# POWER.net
KiCad netlist of a schematic drawn in Altium Designer
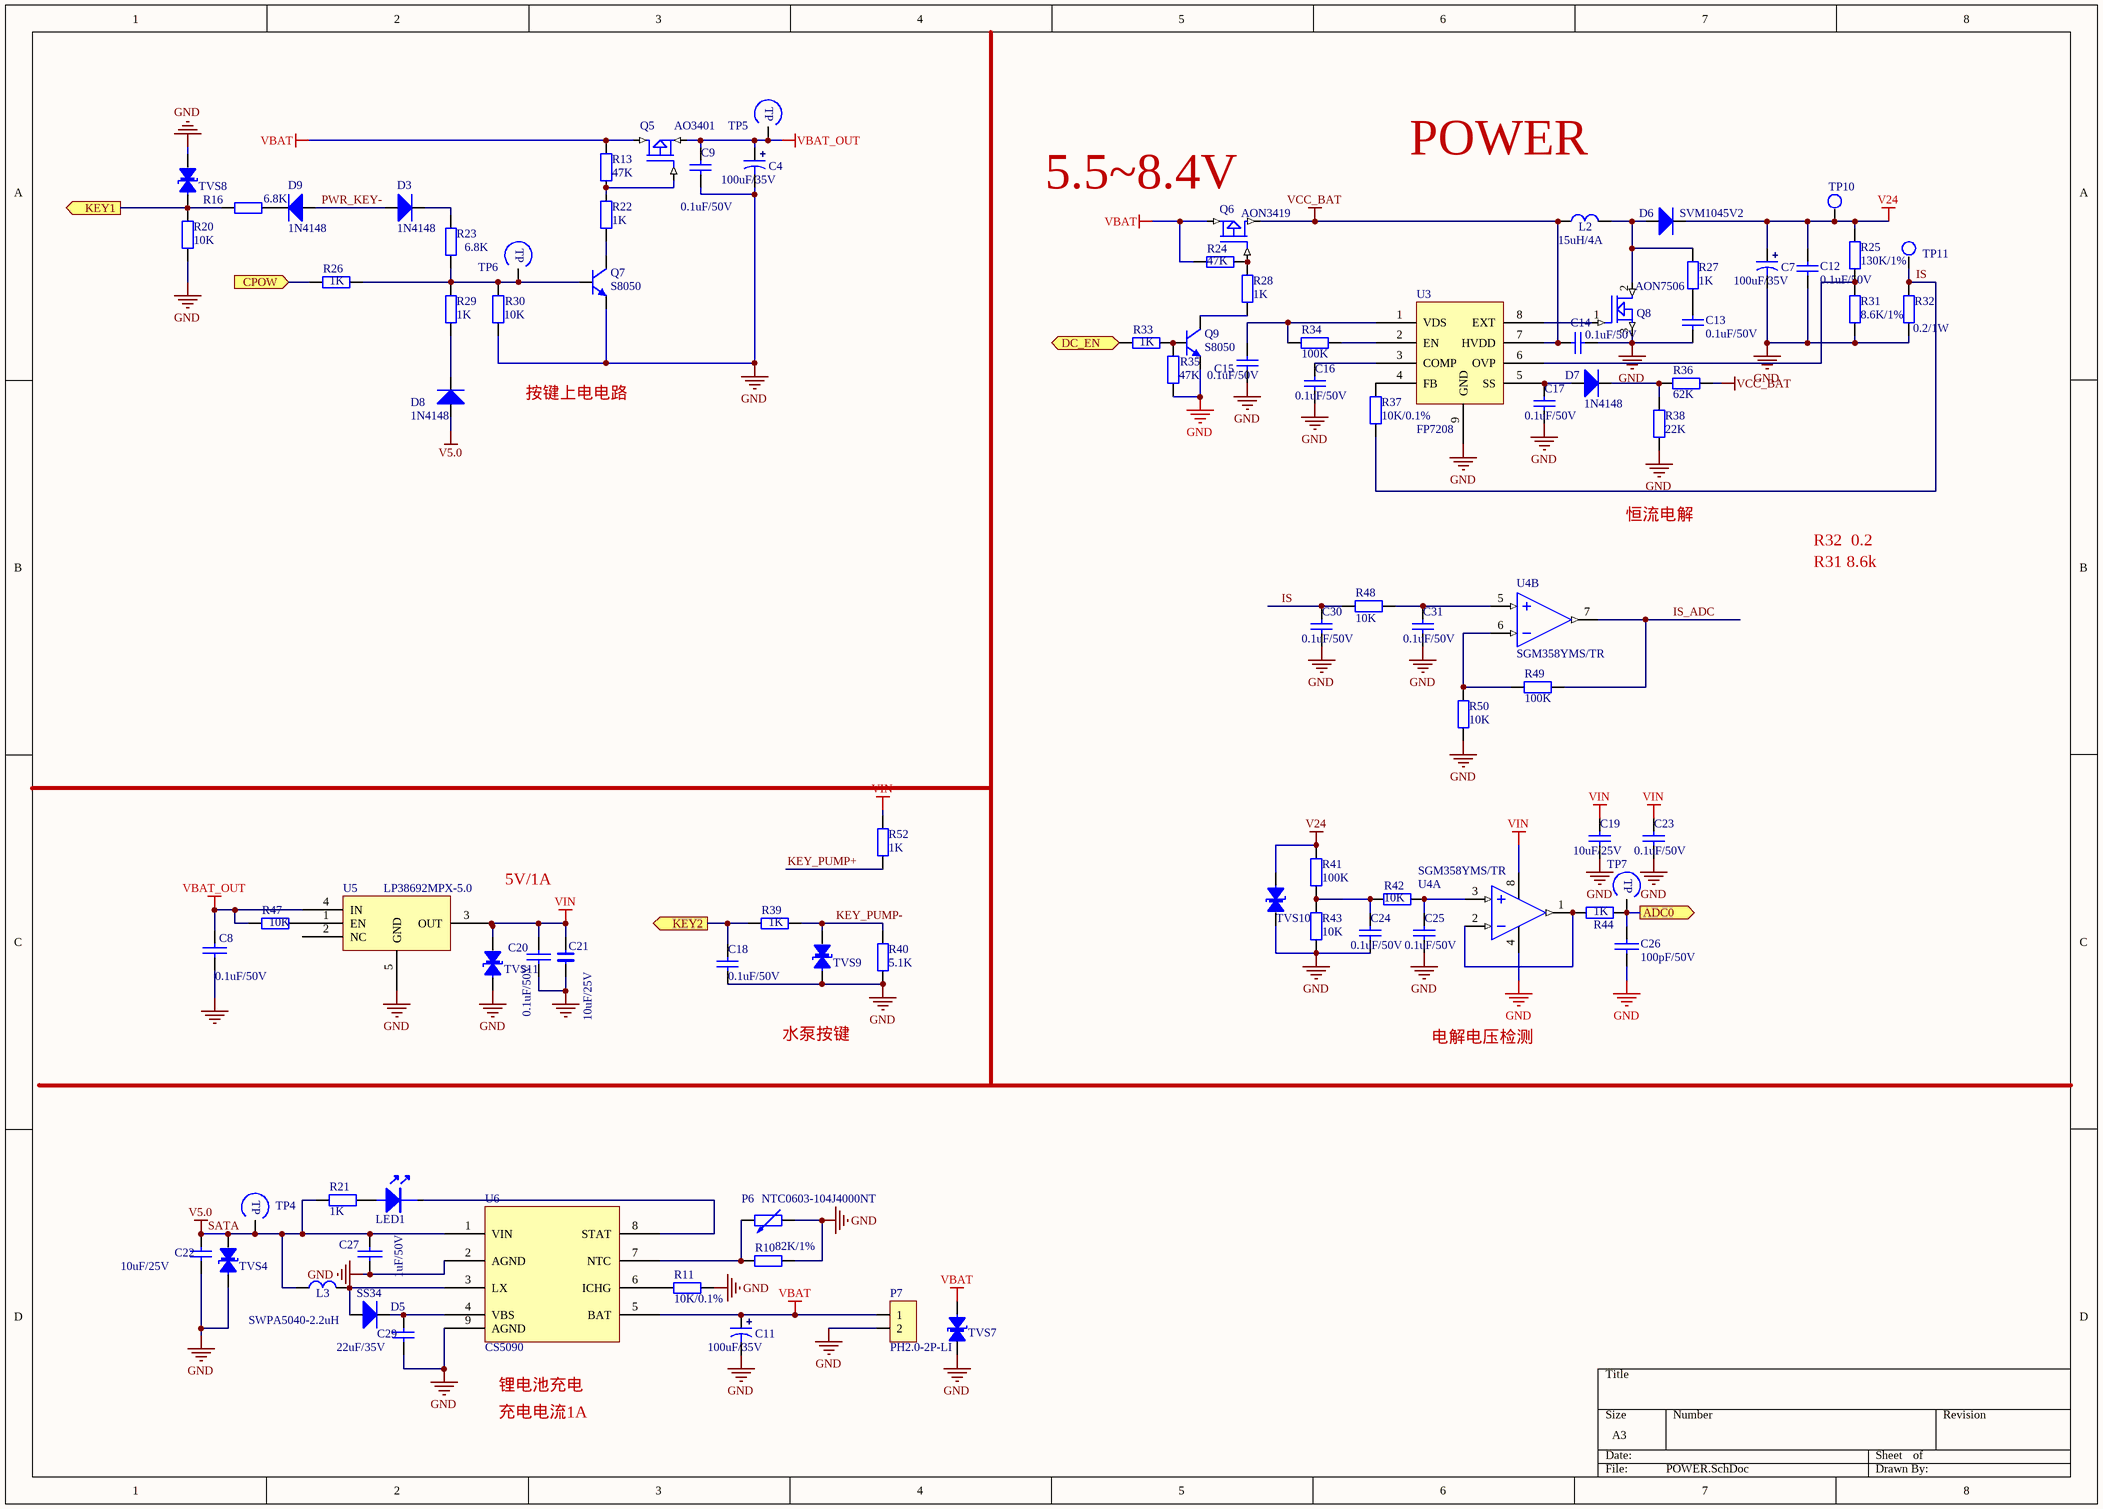
[diagram p0: POWER.SchDoc]

(export (version "E")
  (design (tool "Eeschema 10.0.6"))
  (components
    (comp (ref "C4")
      (value "100uF/35V")
      (footprint "6*8")
      (description "电解电容")
      (libsource (lib "XiaoyI") (part "CAP2"))
    )
    (comp (ref "C7")
      (value "100uF/35V")
      (footprint "6*8")
      (description "电解电容")
      (libsource (lib "XiaoyI") (part "CAP2"))
    )
    (comp (ref "C8")
      (value "0.1uF/50V")
      (footprint "SMD-0603C")
      (description "Capacitor")
      (libsource (lib "*") (part "CAP"))
    )
    (comp (ref "C9")
      (value "0.1uF/50V")
      (footprint "SMD-0603C")
      (description "贴片电容 10%")
      (libsource (lib "XiaoyI") (part "CAP4"))
    )
    (comp (ref "C11")
      (value "100uF/35V")
      (footprint "6*8")
      (description "电解电容")
      (libsource (lib "XiaoyI") (part "CAP2"))
    )
    (comp (ref "C12")
      (value "0.1uF/50V")
      (footprint "SMD-0603C")
      (description "贴片电容 10%")
      (libsource (lib "XiaoyI") (part "CAP4"))
    )
    (comp (ref "C13")
      (value "0.1uF/50V")
      (footprint "SMD-0603C")
      (description "贴片电容 10%")
      (libsource (lib "XiaoyI") (part "CAP4"))
    )
    (comp (ref "C14")
      (value "0.1uF/50V")
      (footprint "SMD-0603C")
      (description "贴片电容 10%")
      (libsource (lib "XiaoyI") (part "CAP4"))
    )
    (comp (ref "C15")
      (value "0.1uF/50V")
      (footprint "SMD-0603C")
      (description "贴片电容 10%")
      (libsource (lib "XiaoyI") (part "CAP4"))
    )
    (comp (ref "C16")
      (value "0.1uF/50V")
      (footprint "SMD-0603C")
      (description "贴片电容 10%")
      (libsource (lib "XiaoyI") (part "CAP4"))
    )
    (comp (ref "C17")
      (value "0.1uF/50V")
      (footprint "SMD-0603C")
      (description "贴片电容 10%")
      (libsource (lib "XiaoyI") (part "CAP4"))
    )
    (comp (ref "C18")
      (value "0.1uF/50V")
      (footprint "SMD-0603C")
      (description "贴片电容 10%")
      (libsource (lib "XiaoyI") (part "CAP4"))
    )
    (comp (ref "C19")
      (value "10uF/25V")
      (footprint "SMD-0603C")
      (description "贴片电容 10%")
      (libsource (lib "XiaoyI") (part "CAP4"))
    )
    (comp (ref "C20")
      (value "0.1uF/50V")
      (footprint "SMD-0603C")
      (description "Capacitor")
      (libsource (lib "*") (part "CAP"))
    )
    (comp (ref "C21")
      (value "10uF/25V")
      (footprint "SMD-0603C")
      (description "C")
      (libsource (lib "Top") (part "C"))
    )
    (comp (ref "C22")
      (value "10uF/25V")
      (footprint "SMD-0603C")
      (description "贴片电容 20%")
      (libsource (lib "XiaoyI") (part "CAP4"))
    )
    (comp (ref "C23")
      (value "0.1uF/50V")
      (footprint "SMD-0603C")
      (description "贴片电容 10%")
      (libsource (lib "XiaoyI") (part "CAP4"))
    )
    (comp (ref "C24")
      (value "0.1uF/50V")
      (footprint "SMD-0603C")
      (description "贴片电容 10%")
      (libsource (lib "XiaoyI") (part "CAP4"))
    )
    (comp (ref "C25")
      (value "0.1uF/50V")
      (footprint "SMD-0603C")
      (description "贴片电容 10%")
      (libsource (lib "XiaoyI") (part "CAP4"))
    )
    (comp (ref "C26")
      (value "100pF/50V")
      (footprint "SMD-0603C")
      (description "贴片电容 10%")
      (libsource (lib "*") (part "CAP"))
    )
    (comp (ref "C27")
      (value "1uF/50V")
      (footprint "SMD-0603C")
      (description "Capacitor")
      (libsource (lib "*") (part "CAP"))
    )
    (comp (ref "C29")
      (value "22uF/35V")
      (footprint "SMD-0603C")
      (description "贴片电容 10%")
      (libsource (lib "XiaoyI") (part "CAP4"))
    )
    (comp (ref "C30")
      (value "0.1uF/50V")
      (footprint "SMD-0603C")
      (description "贴片电容 10%")
      (libsource (lib "XiaoyI") (part "CAP4"))
    )
    (comp (ref "C31")
      (value "0.1uF/50V")
      (footprint "SMD-0603C")
      (description "贴片电容 10%")
      (libsource (lib "XiaoyI") (part "CAP4"))
    )
    (comp (ref "D3")
      (value "1N4148")
      (footprint "SOD-523")
      (description "小封装二极管")
      (libsource (lib "XiaoyI") (part "DIODE2"))
    )
    (comp (ref "D5")
      (value "SS34")
      (footprint "DO-214-AC")
      (description "肖特基二极管")
      (libsource (lib "XiaoyI") (part "DIODE2"))
    )
    (comp (ref "D6")
      (value "SVM1045V2")
      (footprint "TO227")
      (description "肖特基二极管")
      (libsource (lib "XiaoyI") (part "DIODE2"))
    )
    (comp (ref "D7")
      (value "1N4148")
      (footprint "SOD-523")
      (description "小封装二极管")
      (libsource (lib "XiaoyI") (part "DIODE2"))
    )
    (comp (ref "D8")
      (value "1N4148")
      (footprint "SOD-523")
      (description "小封装二极管")
      (libsource (lib "XiaoyI") (part "DIODE2"))
    )
    (comp (ref "D9")
      (value "1N4148")
      (footprint "SOD-523")
      (description "小封装二极管")
      (libsource (lib "XiaoyI") (part "DIODE2"))
    )
    (comp (ref "L2")
      (value "15uH/4A")
      (footprint "INDUCTOR7*7")
      (description "10uH 1A")
      (libsource (lib "XiaoyI") (part "Inductor1"))
    )
    (comp (ref "L3")
      (value "SWPA5040-2.2uH")
      (footprint "INDUCTOR_5*5")
      (description "10uH 1A")
      (libsource (lib "XiaoyI") (part "Inductor1"))
    )
    (comp (ref "LED1")
      (value "蓝光 3528")
      (footprint "SMD-0603D")
      (description "LED 3528 蓝")
      (libsource (lib "XiaoyI") (part "LED0"))
    )
    (comp (ref "P6")
      (value "NTC0603-104J4000NT")
      (footprint "SMD-0603")
      (description "卧贴")
      (libsource (lib "ABB") (part "RES3"))
    )
    (comp (ref "P7")
      (value "PH2.0-2P-LI")
      (footprint "2*2.54mmSMT")
      (description "间距2.0mm 立贴 2Pin")
      (libsource (lib "XiaoyI") (part "SIP-2"))
    )
    (comp (ref "Q5")
      (value "AO3401")
      (footprint "SOT-23")
      (description "MOSFET P")
      (libsource (lib "ABB") (part "MOSFET P"))
    )
    (comp (ref "Q6")
      (value "AON3419")
      (footprint "DFN3*3-8")
      (description "MOSFET-P")
      (libsource (lib "XiaoyI") (part "MOSFET-P-B"))
    )
    (comp (ref "Q7")
      (value "S8050")
      (footprint "SOT-23")
      (description "NPN")
      (libsource (lib "XiaoyI") (part "NPN-1"))
    )
    (comp (ref "Q8")
      (value "AON7506")
      (footprint "DFN3*3-8")
      (description "MOSFET N")
      (libsource (lib "XiaoyI") (part "MOSFET N"))
    )
    (comp (ref "Q9")
      (value "S8050")
      (footprint "SOT-23")
      (description "NPN")
      (libsource (lib "XiaoyI") (part "NPN-1"))
    )
    (comp (ref "R10")
      (value "82K/1%")
      (footprint "SMD-0603")
      (description "贴片电阻 1%")
      (libsource (lib "") (part "RES2_3"))
    )
    (comp (ref "R11")
      (value "10K/0.1%")
      (footprint "SMD-0603")
      (description "贴片电阻 1%")
      (libsource (lib "") (part "RES2_3"))
    )
    (comp (ref "R13")
      (value "47K")
      (footprint "SMD-0603")
      (description "贴片电阻 5%")
      (libsource (lib "") (part "RES2_1"))
    )
    (comp (ref "R16")
      (value "6.8K")
      (footprint "SMD-0603")
      (description "贴片电阻 5%")
      (libsource (lib "XiaoyI") (part "RES2"))
    )
    (comp (ref "R20")
      (value "10K")
      (footprint "SMD-0603")
      (description "贴片电阻 5%")
      (libsource (lib "") (part "RES2_2"))
    )
    (comp (ref "R21")
      (value "1K")
      (footprint "SMD-0603")
      (description "贴片电阻 5%")
      (libsource (lib "XiaoyI") (part "RES2"))
    )
    (comp (ref "R22")
      (value "1K")
      (footprint "SMD-0603")
      (description "贴片电阻 5%")
      (libsource (lib "") (part "RES2_2"))
    )
    (comp (ref "R23")
      (value "6.8K")
      (footprint "SMD-0603")
      (description "贴片电阻 5%")
      (libsource (lib "") (part "RES2_2"))
    )
    (comp (ref "R24")
      (value "47K")
      (footprint "SMD-0603")
      (description "贴片电阻 5%")
      (libsource (lib "XiaoyI") (part "RES2"))
    )
    (comp (ref "R25")
      (value "130K/1%")
      (footprint "SMD-0603")
      (description "贴片电阻 5%")
      (libsource (lib "") (part "RES2_1"))
    )
    (comp (ref "R26")
      (value "1K")
      (footprint "SMD-0603")
      (description "贴片电阻 5%")
      (libsource (lib "XiaoyI") (part "RES2"))
    )
    (comp (ref "R27")
      (value "1K")
      (footprint "SMD-0603")
      (description "贴片电阻 5%")
      (libsource (lib "") (part "RES2_1"))
    )
    (comp (ref "R28")
      (value "1K")
      (footprint "SMD-0603")
      (description "贴片电阻 5%")
      (libsource (lib "") (part "RES2_1"))
    )
    (comp (ref "R29")
      (value "1K")
      (footprint "SMD-0603")
      (description "贴片电阻 5%")
      (libsource (lib "") (part "RES2_2"))
    )
    (comp (ref "R30")
      (value "10K")
      (footprint "SMD-0603")
      (description "贴片电阻 5%")
      (libsource (lib "") (part "RES2_2"))
    )
    (comp (ref "R31")
      (value "8.6K/1%")
      (footprint "SMD-0603")
      (description "贴片电阻 5%")
      (libsource (lib "") (part "RES2_1"))
    )
    (comp (ref "R32")
      (value "0.2/1W")
      (footprint "2512R")
      (description "贴片电阻 5%")
      (libsource (lib "") (part "RES2_2"))
    )
    (comp (ref "R33")
      (value "1K")
      (footprint "SMD-0603")
      (description "贴片电阻 5%")
      (libsource (lib "XiaoyI") (part "RES2"))
    )
    (comp (ref "R34")
      (value "100K")
      (footprint "SMD-0603")
      (description "贴片电阻 5%")
      (libsource (lib "XiaoyI") (part "RES2"))
    )
    (comp (ref "R35")
      (value "47K")
      (footprint "SMD-0603")
      (description "贴片电阻 5%")
      (libsource (lib "") (part "RES2_2"))
    )
    (comp (ref "R36")
      (value "62K")
      (footprint "SMD-0603")
      (description "贴片电阻 5%")
      (libsource (lib "XiaoyI") (part "RES2"))
    )
    (comp (ref "R37")
      (value "10K/0.1%")
      (footprint "SMD-0603")
      (description "贴片电阻 5%")
      (libsource (lib "") (part "RES2_2"))
    )
    (comp (ref "R38")
      (value "22K")
      (footprint "SMD-0603")
      (description "贴片电阻 5%")
      (libsource (lib "") (part "RES2_1"))
    )
    (comp (ref "R39")
      (value "1K")
      (footprint "SMD-0603")
      (description "贴片电阻 5%")
      (libsource (lib "XiaoyI") (part "RES2"))
    )
    (comp (ref "R40")
      (value "5.1K")
      (footprint "SMD-0603")
      (description "贴片电阻 5%")
      (libsource (lib "") (part "RES2_2"))
    )
    (comp (ref "R41")
      (value "100K")
      (footprint "SMD-0603")
      (description "贴片电阻 1%")
      (libsource (lib "") (part "RES0_2"))
    )
    (comp (ref "R42")
      (value "10K")
      (footprint "SMD-0603")
      (description "贴片电阻 5%")
      (libsource (lib "") (part "RES0_1"))
    )
    (comp (ref "R43")
      (value "10K")
      (footprint "SMD-0603")
      (description "贴片电阻 1%")
      (libsource (lib "") (part "RES0_2"))
    )
    (comp (ref "R44")
      (value "1K")
      (footprint "SMD-0603")
      (description "贴片电阻 1%")
      (libsource (lib "") (part "RES2_3"))
    )
    (comp (ref "R47")
      (value "10K")
      (footprint "SMD-0603")
      (description "贴片电阻 5%")
      (libsource (lib "XiaoyI") (part "RES2"))
    )
    (comp (ref "R48")
      (value "10K")
      (footprint "SMD-0603")
      (description "贴片电阻 5%")
      (libsource (lib "") (part "RES0_1"))
    )
    (comp (ref "R49")
      (value "100K")
      (footprint "SMD-0603")
      (description "贴片电阻 5%")
      (libsource (lib "") (part "RES0_3"))
    )
    (comp (ref "R50")
      (value "10K")
      (footprint "SMD-0603")
      (description "贴片电阻 5%")
      (libsource (lib "ABB") (part "RES0"))
    )
    (comp (ref "R52")
      (value "1K")
      (footprint "SMD-0603")
      (description "贴片电阻 5%")
      (libsource (lib "") (part "RES2_2"))
    )
    (comp (ref "TP4")
      (value "testpoint")
      (footprint "TP")
      (description "测试点")
      (libsource (lib "XiaoyI") (part "TP-1"))
    )
    (comp (ref "TP5")
      (value "testpoint")
      (footprint "TP")
      (description "测试点")
      (libsource (lib "XiaoyI") (part "TP-1"))
    )
    (comp (ref "TP6")
      (value "testpoint")
      (footprint "TP")
      (description "测试点")
      (libsource (lib "XiaoyI") (part "TP-1"))
    )
    (comp (ref "TP7")
      (value "testpoint")
      (footprint "TP")
      (description "测试点")
      (libsource (lib "XiaoyI") (part "TP-1"))
    )
    (comp (ref "TP10") (value "TPS") (footprint "HOLE") (libsource (lib "stm32") (part "TPS")))
    (comp (ref "TP11") (value "TPS") (footprint "HOLE") (libsource (lib "stm32") (part "TPS")))
    (comp (ref "TVS4")
      (value "ESD5Z5.0CT1G")
      (footprint "SOD-523")
      (description "ESD二极管")
      (libsource (lib "XiaoyI") (part "TVS-1"))
    )
    (comp (ref "TVS7")
      (value "SMF9.0CA")
      (footprint "SOD-123")
      (description "ESD二极管")
      (libsource (lib "") (part "TVS-1_1"))
    )
    (comp (ref "TVS8")
      (value "ESD5Z5.0CT1G")
      (footprint "SOD-523")
      (description "ESD二极管")
      (libsource (lib "XiaoyI") (part "TVS-1"))
    )
    (comp (ref "TVS9")
      (value "ESD5Z5.0CT1G")
      (footprint "SOD-523")
      (description "ESD二极管")
      (libsource (lib "XiaoyI") (part "TVS-1"))
    )
    (comp (ref "TVS10")
      (value "SMF24CA")
      (footprint "SOD-123")
      (description "ESD二极管")
      (libsource (lib "") (part "TVS-1_1"))
    )
    (comp (ref "TVS11")
      (value "ESD5Z5.0CT1G")
      (footprint "SOD-523")
      (description "ESD二极管")
      (libsource (lib "XiaoyI") (part "TVS-1"))
    )
    (comp (ref "U3")
      (value "FP7208")
      (footprint "SOP127P600X265_HS-9N")
      (libsource (lib "电解水杯V1.1_ZM_20210702") (part "FP7208"))
    )
    (comp (ref "U4")
      (value "SGM358YMS/TR")
      (footprint "MSOP-8")
      (description "运放")
      (libsource (lib "电解水杯V1.1_ZM_20210702") (part "LM358"))
    )
    (comp (ref "U5")
      (value "LP38692MPX-5.0")
      (footprint "SOT223-5")
      (libsource (lib "stm32") (part "LP38692MPX-5.0"))
    )
    (comp (ref "U6")
      (value "CS5090")
      (footprint "SOP127P600X265_HS-9N")
      (libsource (lib "电解水杯V1.1_ZM_20210702") (part "CS5095E"))
    )
  )
  (nets
    (net (code "1") (name "/ADC0") (class "Default")
      (node (ref "C26") (pin "1") (pinfunction "1_1") (pintype "passive"))
      (node (ref "R44") (pin "1") (pinfunction "1_1") (pintype "passive"))
      (node (ref "TP7") (pin "1") (pinfunction "1_1") (pintype "passive"))
    )
    (net (code "2") (name "/CPOW") (class "Default")
      (node (ref "R26") (pin "1") (pinfunction "1_1") (pintype "passive"))
    )
    (net (code "3") (name "/DC_EN") (class "Default")
      (node (ref "R33") (pin "1") (pinfunction "1_1") (pintype "passive"))
    )
    (net (code "4") (name "/IS") (class "Default")
      (node (ref "C30") (pin "2") (pinfunction "2_2") (pintype "passive"))
      (node (ref "R32") (pin "2") (pinfunction "2_2") (pintype "passive"))
      (node (ref "R37") (pin "1") (pinfunction "1_1") (pintype "passive"))
      (node (ref "R48") (pin "2") (pinfunction "2_2") (pintype "passive"))
      (node (ref "TP11") (pin "1") (pinfunction "1_1") (pintype "passive"))
    )
    (net (code "5") (name "/IS_ADC") (class "Default")
      (node (ref "R49") (pin "2") (pinfunction "2_2") (pintype "passive"))
      (node (ref "U4") (pin "7") (pinfunction "OUT2_7") (pintype "output"))
    )
    (net (code "6") (name "/KEY1") (class "Default")
      (node (ref "R16") (pin "1") (pinfunction "1_1") (pintype "passive"))
      (node (ref "R20") (pin "2") (pinfunction "2_2") (pintype "passive"))
      (node (ref "TVS8") (pin "2") (pinfunction "B_2") (pintype "passive"))
    )
    (net (code "7") (name "/KEY2") (class "Default")
      (node (ref "C18") (pin "2") (pinfunction "2_2") (pintype "passive"))
      (node (ref "R39") (pin "1") (pinfunction "1_1") (pintype "passive"))
    )
    (net (code "8") (name "/KEY_PUMP+") (class "Default")
      (node (ref "R52") (pin "1") (pinfunction "1_1") (pintype "passive"))
    )
    (net (code "9") (name "/KEY_PUMP-") (class "Default")
      (node (ref "R39") (pin "2") (pinfunction "2_2") (pintype "passive"))
      (node (ref "R40") (pin "2") (pinfunction "2_2") (pintype "passive"))
      (node (ref "TVS9") (pin "1") (pinfunction "A_1") (pintype "passive"))
    )
    (net (code "10") (name "/PWR_KEY-") (class "Default")
      (node (ref "D3") (pin "1") (pinfunction "A_1") (pintype "passive"))
      (node (ref "D9") (pin "1") (pinfunction "A_1") (pintype "passive"))
    )
    (net (code "11") (name "GND") (class "Default")
      (node (ref "C11") (pin "2") (pinfunction "2_2") (pintype "passive"))
      (node (ref "C12") (pin "2") (pinfunction "2_2") (pintype "passive"))
      (node (ref "C13") (pin "2") (pinfunction "2_2") (pintype "passive"))
      (node (ref "C14") (pin "1") (pinfunction "1_1") (pintype "passive"))
      (node (ref "C15") (pin "1") (pinfunction "1_1") (pintype "passive"))
      (node (ref "C16") (pin "1") (pinfunction "1_1") (pintype "passive"))
      (node (ref "C17") (pin "1") (pinfunction "1_1") (pintype "passive"))
      (node (ref "C18") (pin "1") (pinfunction "1_1") (pintype "passive"))
      (node (ref "C19") (pin "1") (pinfunction "1_1") (pintype "passive"))
      (node (ref "C20") (pin "2") (pinfunction "2_2") (pintype "passive"))
      (node (ref "C21") (pin "1") (pintype "passive"))
      (node (ref "C22") (pin "1") (pinfunction "1_1") (pintype "passive"))
      (node (ref "C23") (pin "1") (pinfunction "1_1") (pintype "passive"))
      (node (ref "C24") (pin "1") (pinfunction "1_1") (pintype "passive"))
      (node (ref "C25") (pin "1") (pinfunction "1_1") (pintype "passive"))
      (node (ref "C26") (pin "2") (pinfunction "2_2") (pintype "passive"))
      (node (ref "C27") (pin "2") (pinfunction "2_2") (pintype "passive"))
      (node (ref "C29") (pin "1") (pinfunction "1_1") (pintype "passive"))
      (node (ref "C30") (pin "1") (pinfunction "1_1") (pintype "passive"))
      (node (ref "C31") (pin "1") (pinfunction "1_1") (pintype "passive"))
      (node (ref "C4") (pin "2") (pinfunction "2_2") (pintype "passive"))
      (node (ref "C7") (pin "2") (pinfunction "2_2") (pintype "passive"))
      (node (ref "C8") (pin "2") (pinfunction "2_2") (pintype "passive"))
      (node (ref "C9") (pin "1") (pinfunction "1_1") (pintype "passive"))
      (node (ref "P6") (pin "1") (pinfunction "1_1") (pintype "passive"))
      (node (ref "P7") (pin "2") (pinfunction "2_2") (pintype "passive"))
      (node (ref "Q7") (pin "2") (pinfunction "E_2") (pintype "passive"))
      (node (ref "Q8") (pin "3") (pinfunction "S_3") (pintype "output"))
      (node (ref "Q9") (pin "2") (pinfunction "E_2") (pintype "passive"))
      (node (ref "R10") (pin "1") (pinfunction "1_1") (pintype "passive"))
      (node (ref "R11") (pin "1") (pinfunction "1_1") (pintype "passive"))
      (node (ref "R20") (pin "1") (pinfunction "1_1") (pintype "passive"))
      (node (ref "R30") (pin "1") (pinfunction "1_1") (pintype "passive"))
      (node (ref "R31") (pin "2") (pinfunction "2_2") (pintype "passive"))
      (node (ref "R32") (pin "1") (pinfunction "1_1") (pintype "passive"))
      (node (ref "R35") (pin "1") (pinfunction "1_1") (pintype "passive"))
      (node (ref "R38") (pin "2") (pinfunction "2_2") (pintype "passive"))
      (node (ref "R40") (pin "1") (pinfunction "1_1") (pintype "passive"))
      (node (ref "R43") (pin "1") (pinfunction "1_1") (pintype "passive"))
      (node (ref "R50") (pin "2") (pinfunction "2_2") (pintype "passive"))
      (node (ref "TVS10") (pin "1") (pinfunction "A_1") (pintype "passive"))
      (node (ref "TVS11") (pin "2") (pinfunction "B_2") (pintype "passive"))
      (node (ref "TVS4") (pin "2") (pinfunction "B_2") (pintype "passive"))
      (node (ref "TVS7") (pin "1") (pinfunction "A_1") (pintype "passive"))
      (node (ref "TVS8") (pin "1") (pinfunction "A_1") (pintype "passive"))
      (node (ref "TVS9") (pin "2") (pinfunction "B_2") (pintype "passive"))
      (node (ref "U3") (pin "9") (pinfunction "GND_9") (pintype "passive"))
      (node (ref "U4") (pin "4") (pinfunction "V-_4") (pintype "power_in"))
      (node (ref "U5") (pin "5") (pinfunction "GND_5") (pintype "passive"))
      (node (ref "U6") (pin "2") (pinfunction "AGND_2") (pintype "passive"))
      (node (ref "U6") (pin "9") (pinfunction "AGND_9") (pintype "passive"))
    )
    (net (code "12") (name "Net-(C13-Pad1)") (class "Default")
      (node (ref "C13") (pin "1") (pinfunction "1_1") (pintype "passive"))
      (node (ref "R27") (pin "2") (pinfunction "2_2") (pintype "passive"))
    )
    (net (code "13") (name "Net-(C24-Pad2)") (class "Default")
      (node (ref "C24") (pin "2") (pinfunction "2_2") (pintype "passive"))
      (node (ref "R41") (pin "1") (pinfunction "1_1") (pintype "passive"))
      (node (ref "R42") (pin "2") (pinfunction "2_2") (pintype "passive"))
      (node (ref "R43") (pin "2") (pinfunction "2_2") (pintype "passive"))
    )
    (net (code "14") (name "Net-(D3-K)") (class "Default")
      (node (ref "D3") (pin "2") (pinfunction "K_2") (pintype "passive"))
      (node (ref "R23") (pin "2") (pinfunction "2_2") (pintype "passive"))
    )
    (net (code "15") (name "Net-(D5-A)") (class "Default")
      (node (ref "D5") (pin "1") (pinfunction "A_1") (pintype "passive"))
      (node (ref "L3") (pin "2") (pinfunction "2_2") (pintype "passive"))
      (node (ref "U6") (pin "3") (pinfunction "LX_3") (pintype "passive"))
    )
    (net (code "16") (name "Net-(D5-K)") (class "Default")
      (node (ref "C29") (pin "2") (pinfunction "2_2") (pintype "passive"))
      (node (ref "D5") (pin "2") (pinfunction "K_2") (pintype "passive"))
      (node (ref "U6") (pin "4") (pinfunction "VBS_4") (pintype "passive"))
    )
    (net (code "17") (name "Net-(D6-A)") (class "Default")
      (node (ref "D6") (pin "1") (pinfunction "A_1") (pintype "passive"))
      (node (ref "L2") (pin "2") (pinfunction "2_2") (pintype "passive"))
      (node (ref "Q8") (pin "2") (pinfunction "D_2") (pintype "input"))
      (node (ref "R27") (pin "1") (pinfunction "1_1") (pintype "passive"))
    )
    (net (code "18") (name "Net-(D7-A)") (class "Default")
      (node (ref "C17") (pin "2") (pinfunction "2_2") (pintype "passive"))
      (node (ref "D7") (pin "1") (pinfunction "A_1") (pintype "passive"))
      (node (ref "U3") (pin "5") (pinfunction "SS_5") (pintype "passive"))
    )
    (net (code "19") (name "Net-(D7-K)") (class "Default")
      (node (ref "D7") (pin "2") (pinfunction "K_2") (pintype "passive"))
      (node (ref "R36") (pin "1") (pinfunction "1_1") (pintype "passive"))
      (node (ref "R38") (pin "1") (pinfunction "1_1") (pintype "passive"))
    )
    (net (code "20") (name "Net-(D8-K)") (class "Default")
      (node (ref "D8") (pin "2") (pinfunction "K_2") (pintype "passive"))
      (node (ref "R29") (pin "1") (pinfunction "1_1") (pintype "passive"))
    )
    (net (code "21") (name "Net-(D9-K)") (class "Default")
      (node (ref "D9") (pin "2") (pinfunction "K_2") (pintype "passive"))
      (node (ref "R16") (pin "2") (pinfunction "2_2") (pintype "passive"))
    )
    (net (code "22") (name "Net-(LED1-Pad1)") (class "Default")
      (node (ref "LED1") (pin "1") (pinfunction "1_1") (pintype "passive"))
      (node (ref "R21") (pin "2") (pinfunction "2_2") (pintype "passive"))
    )
    (net (code "23") (name "Net-(Q5-G)") (class "Default")
      (node (ref "Q5") (pin "1") (pinfunction "G_1") (pintype "input"))
      (node (ref "R13") (pin "2") (pinfunction "2_2") (pintype "passive"))
      (node (ref "R22") (pin "2") (pinfunction "2_2") (pintype "passive"))
    )
    (net (code "24") (name "Net-(Q6-G)") (class "Default")
      (node (ref "Q6") (pin "1") (pinfunction "G_1") (pintype "input"))
      (node (ref "R24") (pin "2") (pinfunction "2_2") (pintype "passive"))
      (node (ref "R28") (pin "1") (pinfunction "1_1") (pintype "passive"))
    )
    (net (code "25") (name "Net-(Q7-B)") (class "Default")
      (node (ref "Q7") (pin "1") (pinfunction "B_1") (pintype "passive"))
      (node (ref "R23") (pin "1") (pinfunction "1_1") (pintype "passive"))
      (node (ref "R26") (pin "2") (pinfunction "2_2") (pintype "passive"))
      (node (ref "R29") (pin "2") (pinfunction "2_2") (pintype "passive"))
      (node (ref "R30") (pin "2") (pinfunction "2_2") (pintype "passive"))
      (node (ref "TP6") (pin "1") (pinfunction "1_1") (pintype "passive"))
    )
    (net (code "26") (name "Net-(Q7-C)") (class "Default")
      (node (ref "Q7") (pin "3") (pinfunction "C_3") (pintype "passive"))
      (node (ref "R22") (pin "1") (pinfunction "1_1") (pintype "passive"))
    )
    (net (code "27") (name "Net-(Q8-G)") (class "Default")
      (node (ref "Q8") (pin "1") (pinfunction "G_1") (pintype "input"))
      (node (ref "U3") (pin "8") (pinfunction "EXT_8") (pintype "passive"))
    )
    (net (code "28") (name "Net-(Q9-B)") (class "Default")
      (node (ref "Q9") (pin "1") (pinfunction "B_1") (pintype "passive"))
      (node (ref "R33") (pin "2") (pinfunction "2_2") (pintype "passive"))
      (node (ref "R35") (pin "2") (pinfunction "2_2") (pintype "passive"))
    )
    (net (code "29") (name "Net-(Q9-C)") (class "Default")
      (node (ref "Q9") (pin "3") (pinfunction "C_3") (pintype "passive"))
      (node (ref "R28") (pin "2") (pinfunction "2_2") (pintype "passive"))
    )
    (net (code "30") (name "Net-(U3-COMP)") (class "Default")
      (node (ref "C16") (pin "2") (pinfunction "2_2") (pintype "passive"))
      (node (ref "U3") (pin "3") (pinfunction "COMP_3") (pintype "passive"))
    )
    (net (code "31") (name "Net-(U3-EN)") (class "Default")
      (node (ref "R34") (pin "2") (pinfunction "2_2") (pintype "passive"))
      (node (ref "U3") (pin "2") (pinfunction "EN_2") (pintype "passive"))
    )
    (net (code "32") (name "Net-(U3-FB)") (class "Default")
      (node (ref "R37") (pin "2") (pinfunction "2_2") (pintype "passive"))
      (node (ref "U3") (pin "4") (pinfunction "FB_4") (pintype "passive"))
    )
    (net (code "33") (name "Net-(U3-OVP)") (class "Default")
      (node (ref "R25") (pin "2") (pinfunction "2_2") (pintype "passive"))
      (node (ref "R31") (pin "1") (pinfunction "1_1") (pintype "passive"))
      (node (ref "U3") (pin "6") (pinfunction "OVP_6") (pintype "passive"))
    )
    (net (code "34") (name "Net-(U3-VDS)") (class "Default")
      (node (ref "C15") (pin "2") (pinfunction "2_2") (pintype "passive"))
      (node (ref "R34") (pin "1") (pinfunction "1_1") (pintype "passive"))
      (node (ref "U3") (pin "1") (pinfunction "VDS_1") (pintype "passive"))
    )
    (net (code "35") (name "Net-(U4A-IN1+)") (class "Default")
      (node (ref "C25") (pin "2") (pinfunction "2_2") (pintype "passive"))
      (node (ref "R42") (pin "1") (pinfunction "1_1") (pintype "passive"))
      (node (ref "U4") (pin "3") (pinfunction "IN1+_3") (pintype "input"))
    )
    (net (code "36") (name "Net-(U4A-IN1-)") (class "Default")
      (node (ref "R44") (pin "2") (pinfunction "2_2") (pintype "passive"))
      (node (ref "U4") (pin "1") (pinfunction "OUT1_1") (pintype "output"))
      (node (ref "U4") (pin "2") (pinfunction "IN1-_2") (pintype "input"))
    )
    (net (code "37") (name "Net-(U4B-IN2+)") (class "Default")
      (node (ref "C31") (pin "2") (pinfunction "2_2") (pintype "passive"))
      (node (ref "R48") (pin "1") (pinfunction "1_1") (pintype "passive"))
      (node (ref "U4") (pin "5") (pinfunction "IN2+_5") (pintype "input"))
    )
    (net (code "38") (name "Net-(U4B-IN2-)") (class "Default")
      (node (ref "R49") (pin "1") (pinfunction "1_1") (pintype "passive"))
      (node (ref "R50") (pin "1") (pinfunction "1_1") (pintype "passive"))
      (node (ref "U4") (pin "6") (pinfunction "IN2-_6") (pintype "input"))
    )
    (net (code "39") (name "Net-(U5-EN)") (class "Default")
      (node (ref "R47") (pin "2") (pinfunction "2_2") (pintype "passive"))
      (node (ref "U5") (pin "1") (pinfunction "EN_1") (pintype "passive"))
    )
    (net (code "40") (name "Net-(U6-ICHG)") (class "Default")
      (node (ref "R11") (pin "2") (pinfunction "2_2") (pintype "passive"))
      (node (ref "U6") (pin "6") (pinfunction "ICHG_6") (pintype "passive"))
    )
    (net (code "41") (name "Net-(U6-NTC)") (class "Default")
      (node (ref "P6") (pin "2") (pinfunction "2_2") (pintype "passive"))
      (node (ref "R10") (pin "2") (pinfunction "2_2") (pintype "passive"))
      (node (ref "U6") (pin "7") (pinfunction "NTC_7") (pintype "passive"))
    )
    (net (code "42") (name "Net-(U6-STAT)") (class "Default")
      (node (ref "LED1") (pin "2") (pinfunction "2_2") (pintype "passive"))
      (node (ref "U6") (pin "8") (pinfunction "STAT_8") (pintype "passive"))
    )
    (net (code "43") (name "V5.0") (class "Default")
      (node (ref "C22") (pin "2") (pinfunction "2_2") (pintype "passive"))
      (node (ref "C27") (pin "1") (pinfunction "1_1") (pintype "passive"))
      (node (ref "D8") (pin "1") (pinfunction "A_1") (pintype "passive"))
      (node (ref "L3") (pin "1") (pinfunction "1_1") (pintype "passive"))
      (node (ref "R21") (pin "1") (pinfunction "1_1") (pintype "passive"))
      (node (ref "TP4") (pin "1") (pinfunction "1_1") (pintype "passive"))
      (node (ref "TVS4") (pin "1") (pinfunction "A_1") (pintype "passive"))
      (node (ref "U6") (pin "1") (pinfunction "VIN_1") (pintype "passive"))
    )
    (net (code "44") (name "V24") (class "Default")
      (node (ref "C12") (pin "1") (pinfunction "1_1") (pintype "passive"))
      (node (ref "C7") (pin "1") (pinfunction "1_1") (pintype "passive"))
      (node (ref "D6") (pin "2") (pinfunction "K_2") (pintype "passive"))
      (node (ref "R25") (pin "1") (pinfunction "1_1") (pintype "passive"))
      (node (ref "R41") (pin "2") (pinfunction "2_2") (pintype "passive"))
      (node (ref "TP10") (pin "1") (pinfunction "1_1") (pintype "passive"))
      (node (ref "TVS10") (pin "2") (pinfunction "B_2") (pintype "passive"))
    )
    (net (code "45") (name "VBAT") (class "Default")
      (node (ref "C11") (pin "1") (pinfunction "1_1") (pintype "passive"))
      (node (ref "P7") (pin "1") (pinfunction "1_1") (pintype "passive"))
      (node (ref "Q5") (pin "2") (pinfunction "D_2") (pintype "input"))
      (node (ref "Q6") (pin "3") (pinfunction "S_3") (pintype "input"))
      (node (ref "R13") (pin "1") (pinfunction "1_1") (pintype "passive"))
      (node (ref "R24") (pin "1") (pinfunction "1_1") (pintype "passive"))
      (node (ref "TVS7") (pin "2") (pinfunction "B_2") (pintype "passive"))
      (node (ref "U6") (pin "5") (pinfunction "BAT_5") (pintype "passive"))
    )
    (net (code "46") (name "VBAT_OUT") (class "Default")
      (node (ref "C4") (pin "1") (pinfunction "1_1") (pintype "passive"))
      (node (ref "C8") (pin "1") (pinfunction "1_1") (pintype "passive"))
      (node (ref "C9") (pin "2") (pinfunction "2_2") (pintype "passive"))
      (node (ref "Q5") (pin "3") (pinfunction "S_3") (pintype "input"))
      (node (ref "R47") (pin "1") (pinfunction "1_1") (pintype "passive"))
      (node (ref "TP5") (pin "1") (pinfunction "1_1") (pintype "passive"))
      (node (ref "U5") (pin "4") (pinfunction "IN_4") (pintype "passive"))
    )
    (net (code "47") (name "VCC_BAT") (class "Default")
      (node (ref "C14") (pin "2") (pinfunction "2_2") (pintype "passive"))
      (node (ref "L2") (pin "1") (pinfunction "1_1") (pintype "passive"))
      (node (ref "Q6") (pin "2") (pinfunction "D_2") (pintype "output"))
      (node (ref "R36") (pin "2") (pinfunction "2_2") (pintype "passive"))
      (node (ref "U3") (pin "7") (pinfunction "HVDD_7") (pintype "passive"))
    )
    (net (code "48") (name "VIN") (class "Default")
      (node (ref "C19") (pin "2") (pinfunction "2_2") (pintype "passive"))
      (node (ref "C20") (pin "1") (pinfunction "1_1") (pintype "passive"))
      (node (ref "C21") (pin "2") (pintype "passive"))
      (node (ref "C23") (pin "2") (pinfunction "2_2") (pintype "passive"))
      (node (ref "R52") (pin "2") (pinfunction "2_2") (pintype "passive"))
      (node (ref "TVS11") (pin "1") (pinfunction "A_1") (pintype "passive"))
      (node (ref "U4") (pin "8") (pinfunction "V+_8") (pintype "power_in"))
      (node (ref "U5") (pin "3") (pinfunction "OUT_3") (pintype "passive"))
    )
    (net (code "49") (name "unconnected-(U5-NC-Pad2)") (class "Default")
      (node (ref "U5") (pin "2") (pinfunction "NC_2") (pintype "passive"))
    )
  )
)
